# MeterMaid.net
KiCad netlist of a schematic drawn in EAGLE
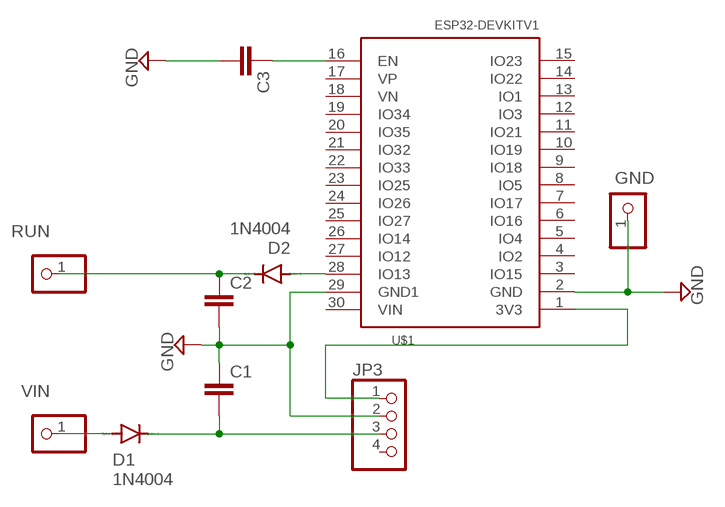
[diagram p0: schematic, sheet 1]

(export (version "E")
  (design (tool "Eeschema 10.0.6"))
  (components
    (comp (ref "C1")
      (value "C-EU025-050X050")
      (footprint "eagle-import:C025-050X050")
      (libsource (lib "eagle-import") (part "C-EU025-050X050"))
    )
    (comp (ref "C2")
      (value "C-EU025-050X050")
      (footprint "eagle-import:C025-050X050")
      (libsource (lib "eagle-import") (part "C-EU025-050X050"))
    )
    (comp (ref "C3")
      (value "C-EU025-050X050")
      (footprint "eagle-import:C025-050X050")
      (libsource (lib "eagle-import") (part "C-EU025-050X050"))
    )
    (comp (ref "D1")
      (value "1N4004")
      (footprint "eagle-import:DO41-10")
      (libsource (lib "eagle-import") (part "1N4004"))
    )
    (comp (ref "D2")
      (value "1N4004")
      (footprint "eagle-import:DO41-10")
      (libsource (lib "eagle-import") (part "1N4004"))
    )
    (comp (ref "GND")
      (value "PINHD-1X1")
      (footprint "eagle-import:1X01")
      (libsource (lib "eagle-import") (part "PINHD-1X1"))
    )
    (comp (ref "JP3")
      (value "PINHD-1X4")
      (footprint "eagle-import:1X04")
      (libsource (lib "eagle-import") (part "PINHD-1X4"))
    )
    (comp (ref "RUN")
      (value "PINHD-1X1")
      (footprint "eagle-import:1X01")
      (libsource (lib "eagle-import") (part "PINHD-1X1"))
    )
    (comp (ref "U$1")
      (value "ESP32DEVKITV1")
      (footprint "eagle-import:ESP32-DEVKITV1")
      (libsource (lib "eagle-import") (part "ESP32DEVKITV1"))
    )
    (comp (ref "VIN")
      (value "PINHD-1X1")
      (footprint "eagle-import:1X01")
      (libsource (lib "eagle-import") (part "PINHD-1X1"))
    )
  )
  (nets
    (net (code "1") (name "GND") (class "Default")
      (node (ref "C1") (pin "1") (pinfunction "1_1") (pintype "passive"))
      (node (ref "C2") (pin "2") (pinfunction "2_2") (pintype "passive"))
      (node (ref "C3") (pin "2") (pinfunction "2_2") (pintype "passive"))
      (node (ref "GND") (pin "1") (pinfunction "1_1") (pintype "passive"))
      (node (ref "JP3") (pin "2") (pinfunction "2_2") (pintype "passive"))
      (node (ref "U$1") (pin "2") (pinfunction "GND_2") (pintype "bidirectional"))
      (node (ref "U$1") (pin "29") (pinfunction "GND1_29") (pintype "bidirectional"))
    )
    (net (code "2") (name "Net-(C1-Pad2)") (class "Default")
      (node (ref "C1") (pin "2") (pinfunction "2_2") (pintype "passive"))
      (node (ref "D1") (pin "C") (pinfunction "C_C") (pintype "passive"))
      (node (ref "JP3") (pin "3") (pinfunction "3_3") (pintype "passive"))
    )
    (net (code "3") (name "Net-(C2-Pad1)") (class "Default")
      (node (ref "C2") (pin "1") (pinfunction "1_1") (pintype "passive"))
      (node (ref "D2") (pin "C") (pinfunction "C_C") (pintype "passive"))
      (node (ref "RUN") (pin "1") (pinfunction "1_1") (pintype "passive"))
    )
    (net (code "4") (name "Net-(D1-PadA)") (class "Default")
      (node (ref "D1") (pin "A") (pinfunction "A_A") (pintype "passive"))
      (node (ref "VIN") (pin "1") (pinfunction "1_1") (pintype "passive"))
    )
    (net (code "5") (name "Net-(U$1-3V3)") (class "Default")
      (node (ref "JP3") (pin "1") (pinfunction "1_1") (pintype "passive"))
      (node (ref "U$1") (pin "1") (pinfunction "3V3_1") (pintype "bidirectional"))
    )
    (net (code "6") (name "Net-(U$1-EN)") (class "Default")
      (node (ref "C3") (pin "1") (pinfunction "1_1") (pintype "passive"))
      (node (ref "U$1") (pin "16") (pinfunction "EN_16") (pintype "bidirectional"))
    )
    (net (code "7") (name "Net-(U$1-IO13)") (class "Default")
      (node (ref "D2") (pin "A") (pinfunction "A_A") (pintype "passive"))
      (node (ref "U$1") (pin "28") (pinfunction "IO13_28") (pintype "bidirectional"))
    )
    (net (code "8") (name "unconnected-(JP3-Pad4)") (class "Default")
      (node (ref "JP3") (pin "4") (pinfunction "4_4") (pintype "passive"))
    )
    (net (code "9") (name "unconnected-(U$1-IO1-Pad13)") (class "Default")
      (node (ref "U$1") (pin "13") (pinfunction "IO1_13") (pintype "bidirectional"))
    )
    (net (code "10") (name "unconnected-(U$1-IO2-Pad4)") (class "Default")
      (node (ref "U$1") (pin "4") (pinfunction "IO2_4") (pintype "bidirectional"))
    )
    (net (code "11") (name "unconnected-(U$1-IO3-Pad12)") (class "Default")
      (node (ref "U$1") (pin "12") (pinfunction "IO3_12") (pintype "bidirectional"))
    )
    (net (code "12") (name "unconnected-(U$1-IO4-Pad5)") (class "Default")
      (node (ref "U$1") (pin "5") (pinfunction "IO4_5") (pintype "bidirectional"))
    )
    (net (code "13") (name "unconnected-(U$1-IO5-Pad8)") (class "Default")
      (node (ref "U$1") (pin "8") (pinfunction "IO5_8") (pintype "bidirectional"))
    )
    (net (code "14") (name "unconnected-(U$1-IO12-Pad27)") (class "Default")
      (node (ref "U$1") (pin "27") (pinfunction "IO12_27") (pintype "bidirectional"))
    )
    (net (code "15") (name "unconnected-(U$1-IO14-Pad26)") (class "Default")
      (node (ref "U$1") (pin "26") (pinfunction "IO14_26") (pintype "bidirectional"))
    )
    (net (code "16") (name "unconnected-(U$1-IO15-Pad3)") (class "Default")
      (node (ref "U$1") (pin "3") (pinfunction "IO15_3") (pintype "bidirectional"))
    )
    (net (code "17") (name "unconnected-(U$1-IO16-Pad6)") (class "Default")
      (node (ref "U$1") (pin "6") (pinfunction "IO16_6") (pintype "bidirectional"))
    )
    (net (code "18") (name "unconnected-(U$1-IO17-Pad7)") (class "Default")
      (node (ref "U$1") (pin "7") (pinfunction "IO17_7") (pintype "bidirectional"))
    )
    (net (code "19") (name "unconnected-(U$1-IO18-Pad9)") (class "Default")
      (node (ref "U$1") (pin "9") (pinfunction "IO18_9") (pintype "bidirectional"))
    )
    (net (code "20") (name "unconnected-(U$1-IO19-Pad10)") (class "Default")
      (node (ref "U$1") (pin "10") (pinfunction "IO19_10") (pintype "bidirectional"))
    )
    (net (code "21") (name "unconnected-(U$1-IO21-Pad11)") (class "Default")
      (node (ref "U$1") (pin "11") (pinfunction "IO21_11") (pintype "bidirectional"))
    )
    (net (code "22") (name "unconnected-(U$1-IO22-Pad14)") (class "Default")
      (node (ref "U$1") (pin "14") (pinfunction "IO22_14") (pintype "bidirectional"))
    )
    (net (code "23") (name "unconnected-(U$1-IO23-Pad15)") (class "Default")
      (node (ref "U$1") (pin "15") (pinfunction "IO23_15") (pintype "bidirectional"))
    )
    (net (code "24") (name "unconnected-(U$1-IO25-Pad23)") (class "Default")
      (node (ref "U$1") (pin "23") (pinfunction "IO25_23") (pintype "bidirectional"))
    )
    (net (code "25") (name "unconnected-(U$1-IO26-Pad24)") (class "Default")
      (node (ref "U$1") (pin "24") (pinfunction "IO26_24") (pintype "bidirectional"))
    )
    (net (code "26") (name "unconnected-(U$1-IO27-Pad25)") (class "Default")
      (node (ref "U$1") (pin "25") (pinfunction "IO27_25") (pintype "bidirectional"))
    )
    (net (code "27") (name "unconnected-(U$1-IO32-Pad21)") (class "Default")
      (node (ref "U$1") (pin "21") (pinfunction "IO32_21") (pintype "bidirectional"))
    )
    (net (code "28") (name "unconnected-(U$1-IO33-Pad22)") (class "Default")
      (node (ref "U$1") (pin "22") (pinfunction "IO33_22") (pintype "bidirectional"))
    )
    (net (code "29") (name "unconnected-(U$1-IO34-Pad19)") (class "Default")
      (node (ref "U$1") (pin "19") (pinfunction "IO34_19") (pintype "bidirectional"))
    )
    (net (code "30") (name "unconnected-(U$1-IO35-Pad20)") (class "Default")
      (node (ref "U$1") (pin "20") (pinfunction "IO35_20") (pintype "bidirectional"))
    )
    (net (code "31") (name "unconnected-(U$1-VIN-Pad30)") (class "Default")
      (node (ref "U$1") (pin "30") (pinfunction "VIN_30") (pintype "bidirectional"))
    )
    (net (code "32") (name "unconnected-(U$1-VN-Pad18)") (class "Default")
      (node (ref "U$1") (pin "18") (pinfunction "VN_18") (pintype "bidirectional"))
    )
    (net (code "33") (name "unconnected-(U$1-VP-Pad17)") (class "Default")
      (node (ref "U$1") (pin "17") (pinfunction "VP_17") (pintype "bidirectional"))
    )
  )
)
